# 100x100_3_czujniki_busbar.net
KiCad netlist of a schematic drawn in Altium Designer
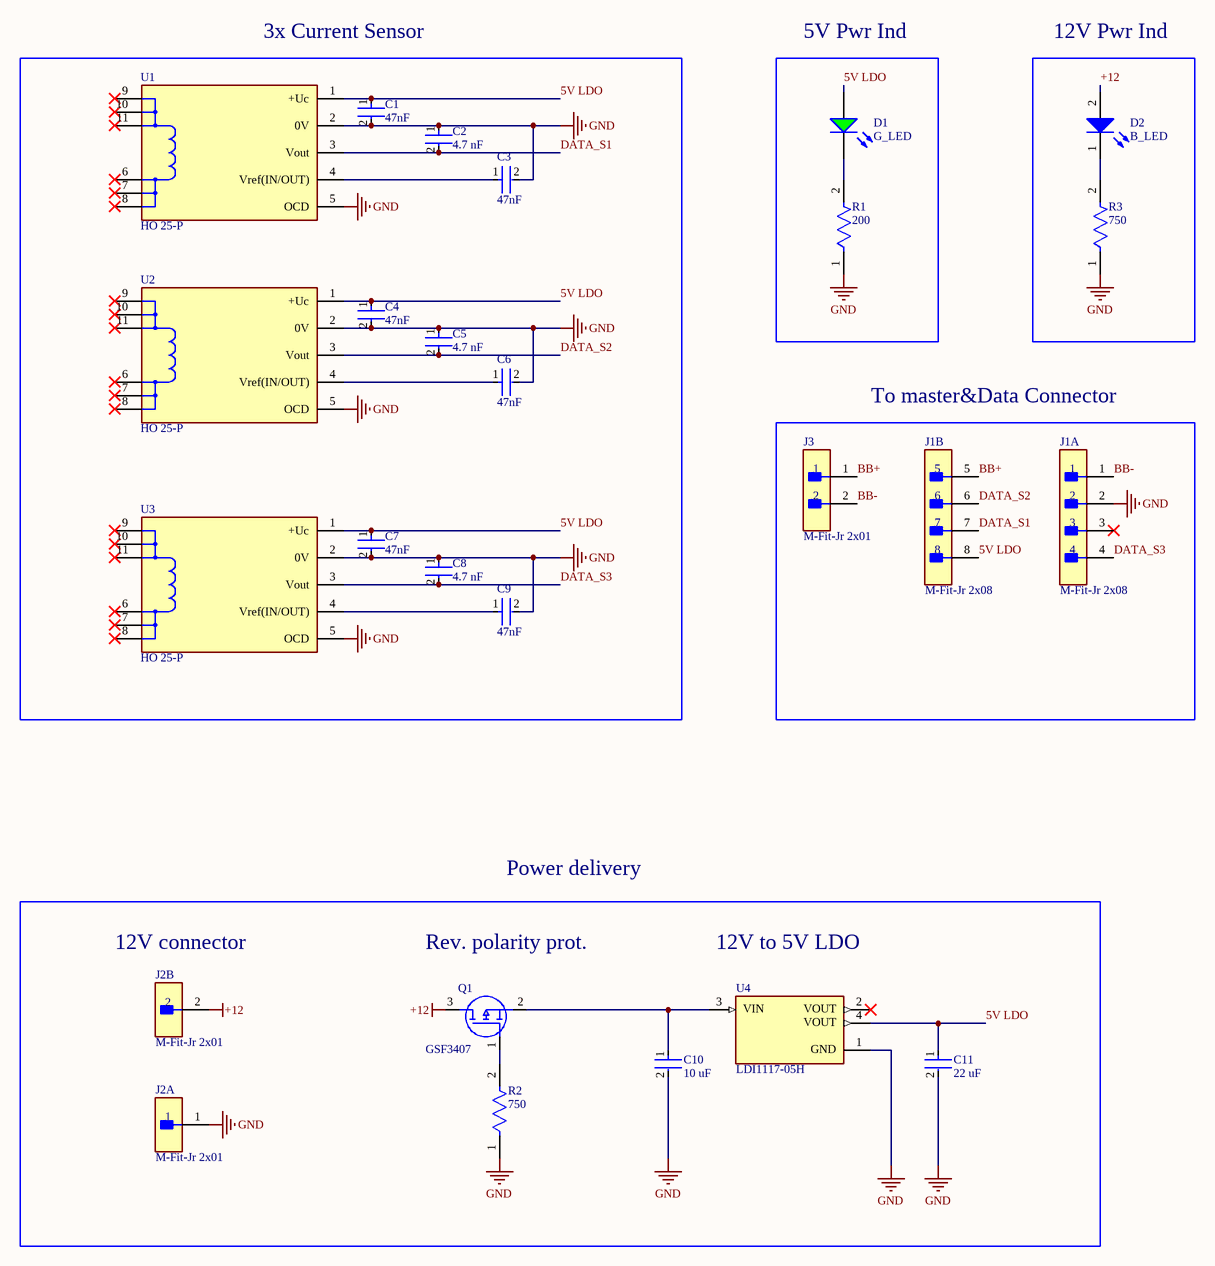
[diagram p0: 100x100_3_czujniki_busbar.SchDoc]

(export (version "E")
  (design (tool "Eeschema 10.0.6"))
  (components
    (comp (ref "C1")
      (value "47nF")
      (footprint "FP-C1206C-EB-MFG")
      (description "0.047 µF ±5% 100V Ceramic Capacitor X7R 1206 (3216 Metric) C1206C473J1RACTU")
      (fields
        (field (name "TOLERANCE") "0.05")
        (field (name "OCTOPART") "https://octopart.com/c1206c473j1ractu-kemet-8206881")
      )
      (libsource (lib "Altium Content Vault") (part "b4654b650e69147ec39a6b967a45e02"))
    )
    (comp (ref "C2")
      (value "4.7 nF")
      (footprint "FP-C1206C-EB-MFG")
      (description "4700 pF ±5% 100V Ceramic Capacitor X7R 1206 (3216 Metric) C1206C472J1RACTU")
      (fields (field (name "MANUFACTURER") "KEMET") (field (name "TOLERANCE") "0.05"))
      (libsource (lib "Altium Content Vault") (part "b4654b650e69147ec39a6b967a45e02"))
    )
    (comp (ref "C3")
      (value "47nF")
      (footprint "FP-C1206C-EB-MFG")
      (description "0.047 µF ±5% 100V Ceramic Capacitor X7R 1206 (3216 Metric) C1206C473J1RACTU")
      (fields
        (field (name "TOLERANCE") "0.05")
        (field (name "OCTOPART") "https://octopart.com/c1206c473j1ractu-kemet-8206881")
      )
      (libsource (lib "Altium Content Vault") (part "b4654b650e69147ec39a6b967a45e02"))
    )
    (comp (ref "C4")
      (value "47nF")
      (footprint "FP-C1206C-EB-MFG")
      (description "0.047 µF ±5% 100V Ceramic Capacitor X7R 1206 (3216 Metric) C1206C473J1RACTU")
      (fields
        (field (name "TOLERANCE") "0.05")
        (field (name "OCTOPART") "https://octopart.com/c1206c473j1ractu-kemet-8206881")
      )
      (libsource (lib "Altium Content Vault") (part "b4654b650e69147ec39a6b967a45e02"))
    )
    (comp (ref "C5")
      (value "4.7 nF")
      (footprint "FP-C1206C-EB-MFG")
      (description "4700 pF ±5% 100V Ceramic Capacitor X7R 1206 (3216 Metric) C1206C472J1RACTU")
      (fields (field (name "MANUFACTURER") "KEMET") (field (name "TOLERANCE") "0.05"))
      (libsource (lib "Altium Content Vault") (part "b4654b650e69147ec39a6b967a45e02"))
    )
    (comp (ref "C6")
      (value "47nF")
      (footprint "FP-C1206C-EB-MFG")
      (description "0.047 µF ±5% 100V Ceramic Capacitor X7R 1206 (3216 Metric) C1206C473J1RACTU")
      (fields
        (field (name "TOLERANCE") "0.05")
        (field (name "OCTOPART") "https://octopart.com/c1206c473j1ractu-kemet-8206881")
      )
      (libsource (lib "Altium Content Vault") (part "b4654b650e69147ec39a6b967a45e02"))
    )
    (comp (ref "C7")
      (value "47nF")
      (footprint "FP-C1206C-EB-MFG")
      (description "0.047 µF ±5% 100V Ceramic Capacitor X7R 1206 (3216 Metric) C1206C473J1RACTU")
      (fields
        (field (name "TOLERANCE") "0.05")
        (field (name "OCTOPART") "https://octopart.com/c1206c473j1ractu-kemet-8206881")
      )
      (libsource (lib "Altium Content Vault") (part "b4654b650e69147ec39a6b967a45e02"))
    )
    (comp (ref "C8")
      (value "4.7 nF")
      (footprint "FP-C1206C-EB-MFG")
      (description "4700 pF ±5% 100V Ceramic Capacitor X7R 1206 (3216 Metric) C1206C472J1RACTU")
      (fields (field (name "MANUFACTURER") "KEMET") (field (name "TOLERANCE") "0.05"))
      (libsource (lib "Altium Content Vault") (part "b4654b650e69147ec39a6b967a45e02"))
    )
    (comp (ref "C9")
      (value "47nF")
      (footprint "FP-C1206C-EB-MFG")
      (description "0.047 µF ±5% 100V Ceramic Capacitor X7R 1206 (3216 Metric) C1206C473J1RACTU")
      (fields
        (field (name "TOLERANCE") "0.05")
        (field (name "OCTOPART") "https://octopart.com/c1206c473j1ractu-kemet-8206881")
      )
      (libsource (lib "Altium Content Vault") (part "b4654b650e69147ec39a6b967a45e02"))
    )
    (comp (ref "C10")
      (value "10 uF")
      (footprint "FP-CL31-IPC_C")
      (description "10 µF ±10% 50V Ceramic Capacitor X5R 1206 (3216 Metric), CL31A106KBHNNNE")
      (fields (field (name "TOLERANCE") "10%") (field (name "MANUFACTURER") "Samsung"))
      (libsource (lib "Altium Content Vault") (part "11868f565c42a9108669ba33697ecf6"))
    )
    (comp (ref "C11")
      (value "22 uF")
      (footprint "FP-CL31-IPC_C")
      (description "22 µF ±10% 16V Ceramic Capacitor X5R 1206 (3216 Metric), CL31A226KOHNNNE")
      (fields (field (name "TOLERANCE") "10%"))
      (libsource (lib "Altium Content Vault") (part "b4654b650e69147ec39a6b967a45e02"))
    )
    (comp (ref "D1")
      (value "G_LED")
      (footprint "LEDC3216X120N")
      (description "Green 571nm LED Indication - Discrete 2V 1206 (3216 Metric)")
      (fields
        (field (name "MANUFACTURER") "Lite-On")
        (field (name "MANUFACTURER PART NUMBER") "LTST-C230KGKT")
      )
      (libsource (lib "3_czujniki_busbar") (part "LTST-C230KGKT"))
    )
    (comp (ref "D2")
      (value "B_LED")
      (footprint "WL-SMCW_1206_150120xx75000")
      (description "Blue 470nm LED Indication - Discrete 3.2V 1206 (3216 Metric), 150120BS75000")
      (libsource (lib "Altium Content Vault") (part "LED_Blue_2A-1K"))
    )
    (comp (ref "J1")
      (value "M-Fit-Jr 2x08")
      (footprint "FP-87427-0802-MFG")
      (description "Connector Header Through Hole, Right Angle 8 position 0.165\" (4.20mm) 87427-0802")
      (libsource (lib "Altium Content Vault") (part "85438c39ca9ef07d43bb2e97c52bc44"))
    )
    (comp (ref "J2")
      (value "M-Fit-Jr 2x01")
      (footprint "FP-26-01-3114-MFG")
      (description "Connector Header Through Hole, Right Angle 2 position, molex mini fit jr 26-01-3114")
      (libsource (lib "Altium Content Vault") (part "5396efca655536962efe5fed4c7110a"))
    )
    (comp (ref "J3")
      (value "M-Fit-Jr 2x01")
      (footprint "FP-39-29-6028-MFG")
      (description "39-29-6028 Connector Header Through Hole 2 position")
      (libsource (lib "Altium Content Vault") (part "3bc925449376181038e59eaffc5286c"))
    )
    (comp (ref "Q1")
      (value "GSF3407")
      (footprint "GSF3407")
      (description "Mosfet, P-ch, Single, -4.1A, -30")
      (fields (field (name "MANUFACTURER") "Good-Ark"))
      (libsource (lib "100x100_3_czujniki_busbar") (part "GSF3407"))
    )
    (comp (ref "R1")
      (value "200")
      (footprint "FP-AC1206-MFG")
      (fields
        (field (name "MANUFACTURER PART NUMBER") "AC1206FR-07200RL")
        (field (name "TOLERANCE") "0.01")
        (field (name "MANUFACTURER") "Yageo")
      )
      (libsource (lib "Altium Content Vault") (part "1029c3af85768c4190bb7ad29bc67b5"))
    )
    (comp (ref "R2")
      (value "750")
      (footprint "FP-CRCW1206-e3-IPC_C")
      (fields (field (name "TOLERANCE") "5%"))
      (libsource (lib "Altium Content Vault") (part "1029c3af85768c4190bb7ad29bc67b5"))
    )
    (comp (ref "R3")
      (value "750")
      (footprint "FP-CRCW1206-e3-IPC_C")
      (fields (field (name "TOLERANCE") "5%"))
      (libsource (lib "Altium Content Vault") (part "1029c3af85768c4190bb7ad29bc67b5"))
    )
    (comp (ref "U1")
      (value "HO 25-P")
      (footprint "HO 25-P")
      (description "Open Loop Current Sensor AC/DC Current 5V Automotive")
      (libsource (lib "test") (part "LEM HO 25-P"))
    )
    (comp (ref "U2")
      (value "HO 25-P")
      (footprint "HO 25-P")
      (description "Open Loop Current Sensor AC/DC Current 5V Automotive")
      (libsource (lib "test") (part "LEM HO 25-P"))
    )
    (comp (ref "U3")
      (value "HO 25-P")
      (footprint "HO 25-P")
      (description "Open Loop Current Sensor AC/DC Current 5V Automotive")
      (libsource (lib "test") (part "LEM HO 25-P"))
    )
    (comp (ref "U4")
      (value "LDI1117-05H")
      (footprint "LDI1117-05H")
      (description "Fixed Positive LDO Regulator")
      (fields (field (name "MANUFACTURER") "Diotec"))
      (libsource (lib "HydrogreenLibrary") (part "LDI1117-05H"))
    )
  )
  (nets
    (net (code "1") (name "+12") (class "Default")
      (node (ref "D2") (pin "2") (pinfunction "A_2") (pintype "passive"))
      (node (ref "J2") (pin "2") (pinfunction "2_2") (pintype "passive"))
      (node (ref "Q1") (pin "3") (pinfunction "D_3") (pintype "passive"))
    )
    (net (code "2") (name "/5V LDO") (class "Default")
      (node (ref "C1") (pin "1") (pinfunction "1_1") (pintype "passive"))
      (node (ref "C11") (pin "1") (pinfunction "1_1") (pintype "passive"))
      (node (ref "C4") (pin "1") (pinfunction "1_1") (pintype "passive"))
      (node (ref "C7") (pin "1") (pinfunction "1_1") (pintype "passive"))
      (node (ref "D1") (pin "1") (pinfunction "A_1") (pintype "passive"))
      (node (ref "J1") (pin "8") (pinfunction "8_8") (pintype "passive"))
      (node (ref "U1") (pin "1") (pinfunction "+Uc_1") (pintype "power_in"))
      (node (ref "U2") (pin "1") (pinfunction "+Uc_1") (pintype "power_in"))
      (node (ref "U3") (pin "1") (pinfunction "+Uc_1") (pintype "power_in"))
      (node (ref "U4") (pin "4") (pintype "output"))
    )
    (net (code "3") (name "/BB+") (class "Default")
      (node (ref "J1") (pin "5") (pinfunction "5_5") (pintype "passive"))
      (node (ref "J3") (pin "1") (pinfunction "1_1") (pintype "passive"))
    )
    (net (code "4") (name "/BB-") (class "Default")
      (node (ref "J1") (pin "1") (pinfunction "1_1") (pintype "passive"))
      (node (ref "J3") (pin "2") (pinfunction "2_2") (pintype "passive"))
    )
    (net (code "5") (name "/DATA_S1") (class "Default")
      (node (ref "C2") (pin "2") (pinfunction "2_2") (pintype "passive"))
      (node (ref "J1") (pin "7") (pinfunction "7_7") (pintype "passive"))
      (node (ref "U1") (pin "3") (pinfunction "Vout_3") (pintype "passive"))
    )
    (net (code "6") (name "/DATA_S2") (class "Default")
      (node (ref "C5") (pin "2") (pinfunction "2_2") (pintype "passive"))
      (node (ref "J1") (pin "6") (pinfunction "6_6") (pintype "passive"))
      (node (ref "U2") (pin "3") (pinfunction "Vout_3") (pintype "passive"))
    )
    (net (code "7") (name "/DATA_S3") (class "Default")
      (node (ref "C8") (pin "2") (pinfunction "2_2") (pintype "passive"))
      (node (ref "J1") (pin "4") (pinfunction "4_4") (pintype "passive"))
      (node (ref "U3") (pin "3") (pinfunction "Vout_3") (pintype "passive"))
    )
    (net (code "8") (name "GND") (class "Default")
      (node (ref "C1") (pin "2") (pinfunction "2_2") (pintype "passive"))
      (node (ref "C10") (pin "2") (pinfunction "2_2") (pintype "passive"))
      (node (ref "C11") (pin "2") (pinfunction "2_2") (pintype "passive"))
      (node (ref "C2") (pin "1") (pinfunction "1_1") (pintype "passive"))
      (node (ref "C3") (pin "2") (pinfunction "2_2") (pintype "passive"))
      (node (ref "C4") (pin "2") (pinfunction "2_2") (pintype "passive"))
      (node (ref "C5") (pin "1") (pinfunction "1_1") (pintype "passive"))
      (node (ref "C6") (pin "2") (pinfunction "2_2") (pintype "passive"))
      (node (ref "C7") (pin "2") (pinfunction "2_2") (pintype "passive"))
      (node (ref "C8") (pin "1") (pinfunction "1_1") (pintype "passive"))
      (node (ref "C9") (pin "2") (pinfunction "2_2") (pintype "passive"))
      (node (ref "J1") (pin "2") (pinfunction "2_2") (pintype "passive"))
      (node (ref "J2") (pin "1") (pinfunction "1_1") (pintype "passive"))
      (node (ref "R1") (pin "1") (pinfunction "1_1") (pintype "passive"))
      (node (ref "R2") (pin "1") (pinfunction "1_1") (pintype "passive"))
      (node (ref "R3") (pin "1") (pinfunction "1_1") (pintype "passive"))
      (node (ref "U1") (pin "2") (pinfunction "0V_2") (pintype "power_in"))
      (node (ref "U1") (pin "5") (pinfunction "OCD_5") (pintype "passive"))
      (node (ref "U2") (pin "2") (pinfunction "0V_2") (pintype "power_in"))
      (node (ref "U2") (pin "5") (pinfunction "OCD_5") (pintype "passive"))
      (node (ref "U3") (pin "2") (pinfunction "0V_2") (pintype "power_in"))
      (node (ref "U3") (pin "5") (pinfunction "OCD_5") (pintype "passive"))
      (node (ref "U4") (pin "1") (pintype "passive"))
    )
    (net (code "9") (name "Net-(D1-K)") (class "Default")
      (node (ref "D1") (pin "2") (pinfunction "K_2") (pintype "passive"))
      (node (ref "R1") (pin "2") (pinfunction "2_2") (pintype "passive"))
    )
    (net (code "10") (name "Net-(D2-K)") (class "Default")
      (node (ref "D2") (pin "1") (pinfunction "K_1") (pintype "passive"))
      (node (ref "R3") (pin "2") (pinfunction "2_2") (pintype "passive"))
    )
    (net (code "11") (name "Net-(Q1-G)") (class "Default")
      (node (ref "Q1") (pin "1") (pinfunction "G_1") (pintype "passive"))
      (node (ref "R2") (pin "2") (pinfunction "2_2") (pintype "passive"))
    )
    (net (code "12") (name "Net-(Q1-S)") (class "Default")
      (node (ref "C10") (pin "1") (pinfunction "1_1") (pintype "passive"))
      (node (ref "Q1") (pin "2") (pinfunction "S_2") (pintype "passive"))
      (node (ref "U4") (pin "3") (pintype "input"))
    )
    (net (code "13") (name "Net-(U1-Vref(IN{slash}OUT))") (class "Default")
      (node (ref "C3") (pin "1") (pinfunction "1_1") (pintype "passive"))
      (node (ref "U1") (pin "4") (pinfunction "Vref(IN/OUT)_4") (pintype "passive"))
    )
    (net (code "14") (name "Net-(U2-Vref(IN{slash}OUT))") (class "Default")
      (node (ref "C6") (pin "1") (pinfunction "1_1") (pintype "passive"))
      (node (ref "U2") (pin "4") (pinfunction "Vref(IN/OUT)_4") (pintype "passive"))
    )
    (net (code "15") (name "Net-(U3-Vref(IN{slash}OUT))") (class "Default")
      (node (ref "C9") (pin "1") (pinfunction "1_1") (pintype "passive"))
      (node (ref "U3") (pin "4") (pinfunction "Vref(IN/OUT)_4") (pintype "passive"))
    )
    (net (code "16") (name "unconnected-(J1-Pad3)") (class "Default")
      (node (ref "J1") (pin "3") (pinfunction "3_3") (pintype "passive+no_connect"))
    )
    (net (code "17") (name "unconnected-(U1-IN-Pad6)") (class "Default")
      (node (ref "U1") (pin "6") (pinfunction "IN_6") (pintype "passive+no_connect"))
    )
    (net (code "18") (name "unconnected-(U1-IN-Pad7)") (class "Default")
      (node (ref "U1") (pin "7") (pinfunction "IN_7") (pintype "passive+no_connect"))
    )
    (net (code "19") (name "unconnected-(U1-IN-Pad8)") (class "Default")
      (node (ref "U1") (pin "8") (pinfunction "IN_8") (pintype "passive+no_connect"))
    )
    (net (code "20") (name "unconnected-(U1-OUT-Pad9)") (class "Default")
      (node (ref "U1") (pin "9") (pinfunction "OUT_9") (pintype "passive+no_connect"))
    )
    (net (code "21") (name "unconnected-(U1-OUT-Pad10)") (class "Default")
      (node (ref "U1") (pin "10") (pinfunction "OUT_10") (pintype "passive+no_connect"))
    )
    (net (code "22") (name "unconnected-(U1-OUT-Pad11)") (class "Default")
      (node (ref "U1") (pin "11") (pinfunction "OUT_11") (pintype "passive+no_connect"))
    )
    (net (code "23") (name "unconnected-(U2-IN-Pad6)") (class "Default")
      (node (ref "U2") (pin "6") (pinfunction "IN_6") (pintype "passive+no_connect"))
    )
    (net (code "24") (name "unconnected-(U2-IN-Pad7)") (class "Default")
      (node (ref "U2") (pin "7") (pinfunction "IN_7") (pintype "passive+no_connect"))
    )
    (net (code "25") (name "unconnected-(U2-IN-Pad8)") (class "Default")
      (node (ref "U2") (pin "8") (pinfunction "IN_8") (pintype "passive+no_connect"))
    )
    (net (code "26") (name "unconnected-(U2-OUT-Pad9)") (class "Default")
      (node (ref "U2") (pin "9") (pinfunction "OUT_9") (pintype "passive+no_connect"))
    )
    (net (code "27") (name "unconnected-(U2-OUT-Pad10)") (class "Default")
      (node (ref "U2") (pin "10") (pinfunction "OUT_10") (pintype "passive+no_connect"))
    )
    (net (code "28") (name "unconnected-(U2-OUT-Pad11)") (class "Default")
      (node (ref "U2") (pin "11") (pinfunction "OUT_11") (pintype "passive+no_connect"))
    )
    (net (code "29") (name "unconnected-(U3-IN-Pad6)") (class "Default")
      (node (ref "U3") (pin "6") (pinfunction "IN_6") (pintype "passive+no_connect"))
    )
    (net (code "30") (name "unconnected-(U3-IN-Pad7)") (class "Default")
      (node (ref "U3") (pin "7") (pinfunction "IN_7") (pintype "passive+no_connect"))
    )
    (net (code "31") (name "unconnected-(U3-IN-Pad8)") (class "Default")
      (node (ref "U3") (pin "8") (pinfunction "IN_8") (pintype "passive+no_connect"))
    )
    (net (code "32") (name "unconnected-(U3-OUT-Pad9)") (class "Default")
      (node (ref "U3") (pin "9") (pinfunction "OUT_9") (pintype "passive+no_connect"))
    )
    (net (code "33") (name "unconnected-(U3-OUT-Pad10)") (class "Default")
      (node (ref "U3") (pin "10") (pinfunction "OUT_10") (pintype "passive+no_connect"))
    )
    (net (code "34") (name "unconnected-(U3-OUT-Pad11)") (class "Default")
      (node (ref "U3") (pin "11") (pinfunction "OUT_11") (pintype "passive+no_connect"))
    )
    (net (code "35") (name "unconnected-(U4-Pad2)") (class "Default")
      (node (ref "U4") (pin "2") (pintype "output+no_connect"))
    )
  )
)
